# FD-JUL-BB_SCH.net
KiCad netlist of a schematic drawn in Altium Designer
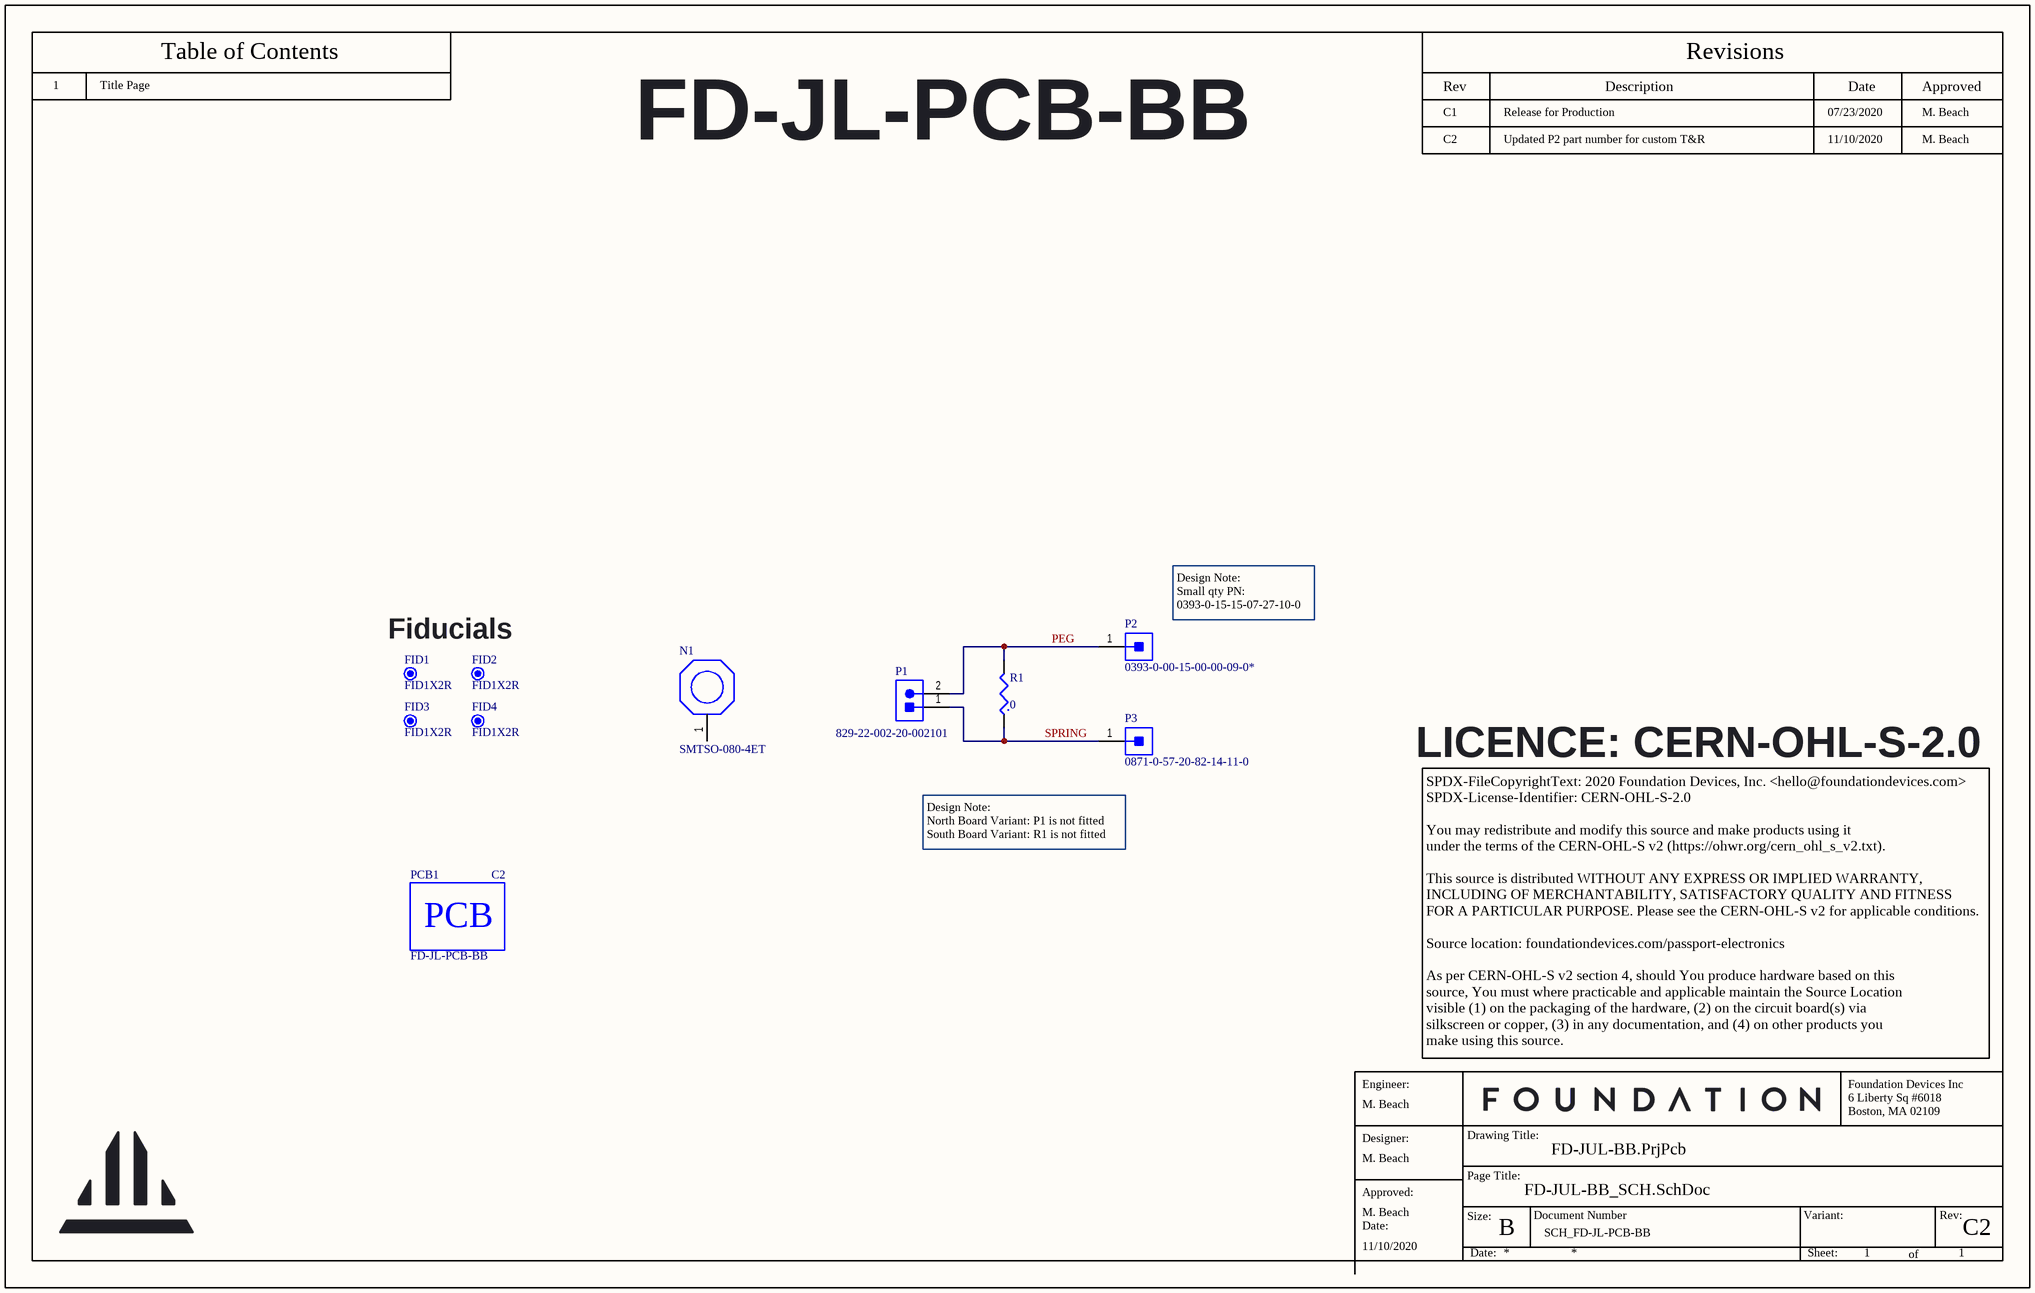
[diagram p0: FD-JUL-BB_SCH.SchDoc]

(export (version "E")
  (design (tool "Eeschema 10.0.6"))
  (components
    (comp (ref "FID1")
      (value "FID1X2R")
      (footprint "FID1X2R")
      (description "Fiducial - Round 1x2mm")
      (libsource (lib "Altium Concord Pro on A365") (part "FID-R-1"))
    )
    (comp (ref "FID2")
      (value "FID1X2R")
      (footprint "FID1X2R")
      (description "Fiducial - Round 1x2mm")
      (libsource (lib "Altium Concord Pro on A365") (part "FID-R-1"))
    )
    (comp (ref "FID3")
      (value "FID1X2R")
      (footprint "FID1X2R")
      (description "Fiducial - Round 1x2mm")
      (libsource (lib "Altium Concord Pro on A365") (part "FID-R-1"))
    )
    (comp (ref "FID4")
      (value "FID1X2R")
      (footprint "FID1X2R")
      (description "Fiducial - Round 1x2mm")
      (libsource (lib "Altium Concord Pro on A365") (part "FID-R-1"))
    )
    (comp (ref "N1")
      (value "SMTSO-080-4ET")
      (footprint "PNENG - SMTSO-080-4ET")
      (description "Surface Mount Nut")
      (libsource (lib "Altium Concord Pro on A365") (part "NUT-1"))
    )
    (comp (ref "P1")
      (value "829-22-002-20-002101")
      (footprint "MIMX - 829-22-002-20-002101_V")
      (description "2 Position Spring Piston Connector Through Hole, Right Angle")
      (libsource (lib "Altium Concord Pro on A365") (part "CN-1P-M-R2"))
    )
    (comp (ref "P2")
      (value "0393-0-00-15-00-00-09-0*")
      (footprint "MIMX - 0393")
      (description "Pin Receptacle Connector 0.065\" ~ 0.082\" (1.65mm ~ 2.08mm) No Tail Solder")
      (libsource (lib "Altium Concord Pro on A365") (part "CN-1P-M-R1"))
    )
    (comp (ref "P3")
      (value "0871-0-57-20-82-14-11-0")
      (footprint "MIMX - 0871-0-15-20-82-14-11-0_V")
      (description "Contact Spring Surface Mount")
      (libsource (lib "Altium Concord Pro on A365") (part "CN-1P-M-R1"))
    )
    (comp (ref "PCB1")
      (value "FD-JL-PCB-BB")
      (description "PCB - Juliet - Battery Board")
      (fields (field (name "REV") "C2"))
      (libsource (lib "Altium Concord Pro on A365") (part "PCB"))
    )
    (comp (ref "R1")
      (value "RES 0 OHM JUMPER 1/8W 0805")
      (footprint "RESC0805(2012)_L")
      (description "0 Ohms Jumper 0.125W, 1/8W Chip Resistor 0805 (2012 Metric)")
      (fields (field (name "RESISTANCE") "0") (field (name "TOLERANCE") "1%"))
      (libsource (lib "Altium Concord Pro on A365") (part "RES-2"))
    )
  )
  (nets
    (net (code "1") (name "/PEG") (class "Default")
      (node (ref "P1") (pin "2") (pinfunction "2_2") (pintype "passive"))
      (node (ref "P2") (pin "1") (pinfunction "1_1") (pintype "passive"))
      (node (ref "R1") (pin "2") (pinfunction "2_2") (pintype "passive"))
    )
    (net (code "2") (name "/SPRING") (class "Default")
      (node (ref "P1") (pin "1") (pinfunction "1_1") (pintype "passive"))
      (node (ref "P3") (pin "1") (pinfunction "1_1") (pintype "passive"))
      (node (ref "R1") (pin "1") (pinfunction "1_1") (pintype "passive"))
    )
    (net (code "3") (name "unconnected-(N1-Nut-Pad1)") (class "Default")
      (node (ref "N1") (pin "1") (pinfunction "Nut_1") (pintype "passive"))
    )
  )
)
